# nano_bt_usb.net
KiCad netlist of a schematic drawn in EAGLE
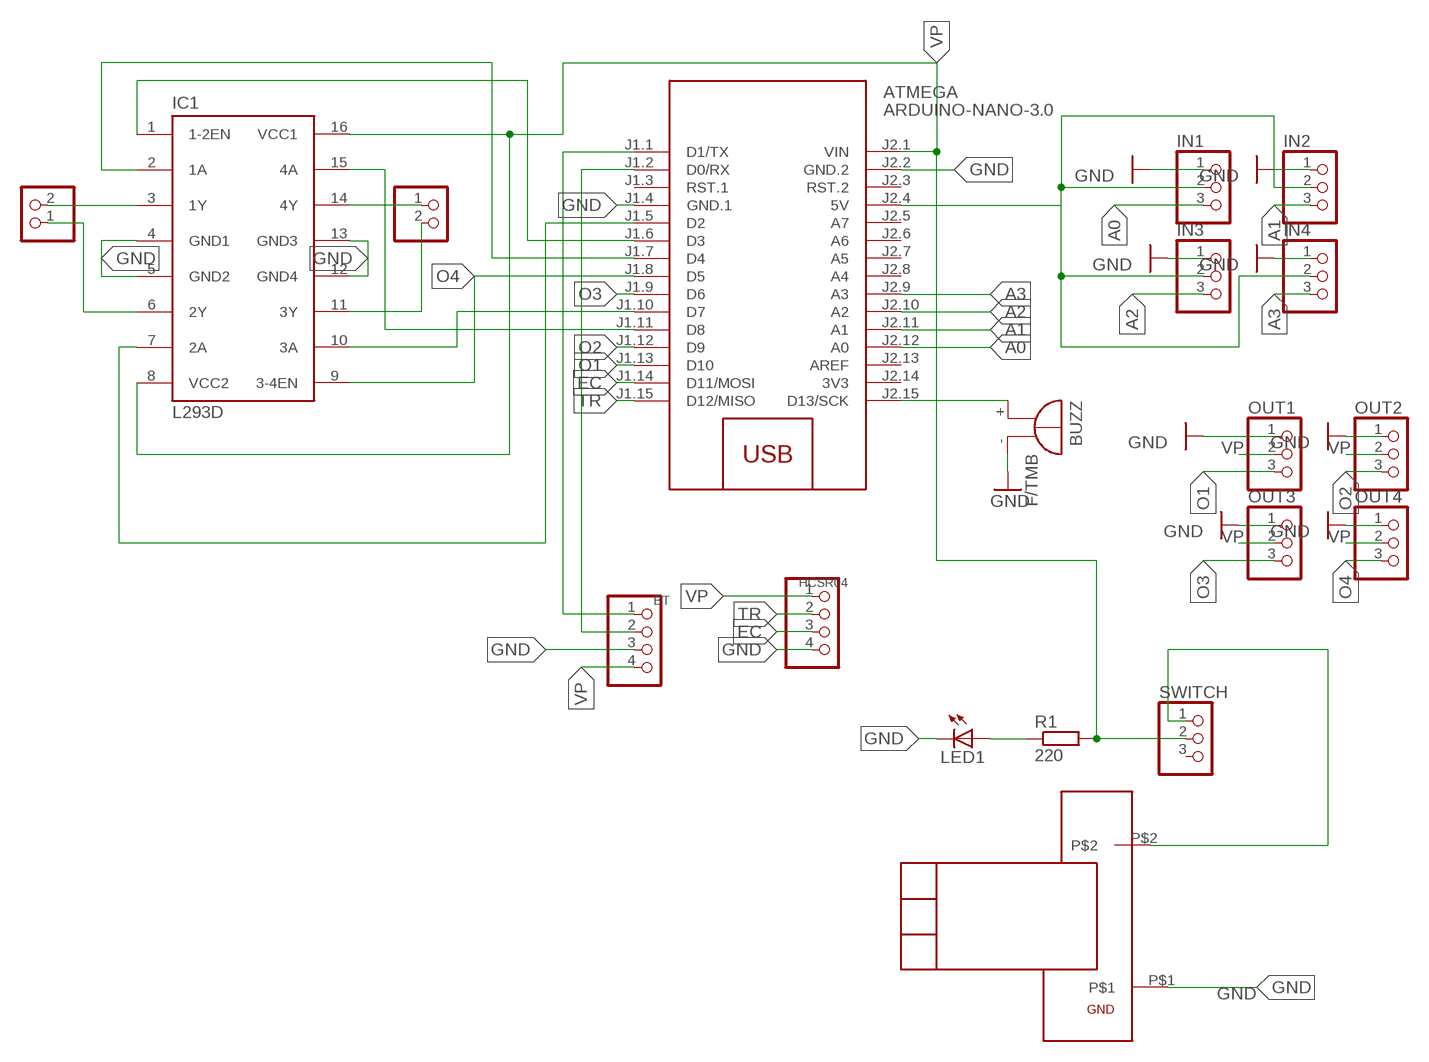
[diagram p0: schematic, sheet 1]

(export (version "E")
  (design (tool "Eeschema 10.0.6"))
  (components
    (comp (ref "ATMEGA")
      (value "ARDUINO-NANO-3.0")
      (footprint "eagle-import:ARDUINO-NANO-3.0")
      (libsource (lib "eagle-import") (part "ARDUINO-NANO-3.0"))
    )
    (comp (ref "BT")
      (value "PINHD-1X4")
      (footprint "eagle-import:1X04")
      (libsource (lib "eagle-import") (part "PINHD-1X4"))
    )
    (comp (ref "BUZZ")
      (value "F/TMB")
      (footprint "eagle-import:F_TMB")
      (libsource (lib "eagle-import") (part "F/TMB"))
    )
    (comp (ref "HCSR04")
      (value "PINHD-1X4")
      (footprint "eagle-import:1X04")
      (libsource (lib "eagle-import") (part "PINHD-1X4"))
    )
    (comp (ref "IC1")
      (value "L293D")
      (footprint "eagle-import:DIL16")
      (libsource (lib "eagle-import") (part "L293D"))
    )
    (comp (ref "IN1")
      (value "PINHD-1X3")
      (footprint "eagle-import:1X03")
      (libsource (lib "eagle-import") (part "PINHD-1X3"))
    )
    (comp (ref "IN2")
      (value "PINHD-1X3")
      (footprint "eagle-import:1X03")
      (libsource (lib "eagle-import") (part "PINHD-1X3"))
    )
    (comp (ref "IN3")
      (value "PINHD-1X3")
      (footprint "eagle-import:1X03")
      (libsource (lib "eagle-import") (part "PINHD-1X3"))
    )
    (comp (ref "IN4")
      (value "PINHD-1X3")
      (footprint "eagle-import:1X03")
      (libsource (lib "eagle-import") (part "PINHD-1X3"))
    )
    (comp (ref "LED1")
      (value "LED3MM")
      (footprint "eagle-import:LED3MM")
      (libsource (lib "eagle-import") (part "LED3MM"))
    )
    (comp (ref "MT1")
      (value "PINHD-1X2")
      (footprint "eagle-import:1X02")
      (libsource (lib "eagle-import") (part "PINHD-1X2"))
    )
    (comp (ref "MT2")
      (value "PINHD-1X2")
      (footprint "eagle-import:1X02")
      (libsource (lib "eagle-import") (part "PINHD-1X2"))
    )
    (comp (ref "OUT1")
      (value "PINHD-1X3")
      (footprint "eagle-import:1X03")
      (libsource (lib "eagle-import") (part "PINHD-1X3"))
    )
    (comp (ref "OUT2")
      (value "PINHD-1X3")
      (footprint "eagle-import:1X03")
      (libsource (lib "eagle-import") (part "PINHD-1X3"))
    )
    (comp (ref "OUT3")
      (value "PINHD-1X3")
      (footprint "eagle-import:1X03")
      (libsource (lib "eagle-import") (part "PINHD-1X3"))
    )
    (comp (ref "OUT4")
      (value "PINHD-1X3")
      (footprint "eagle-import:1X03")
      (libsource (lib "eagle-import") (part "PINHD-1X3"))
    )
    (comp (ref "R1")
      (value "220")
      (footprint "eagle-import:0204_7")
      (libsource (lib "eagle-import") (part "R-EU_0204/7"))
    )
    (comp (ref "SWITCH")
      (value "PINHD-1X3")
      (footprint "eagle-import:1X03")
      (libsource (lib "eagle-import") (part "adafruit_arduino_PINHD-1X3"))
    )
    (comp (ref "U$1")
      (value "MICROUSBMODUL")
      (footprint "eagle-import:MICROUSB")
      (libsource (lib "eagle-import") (part "MICROUSBMODUL"))
    )
  )
  (nets
    (net (code "1") (name "/3V3") (class "Default")
      (node (ref "ATMEGA") (pin "J2.14") (pinfunction "3V3_J2.14") (pintype "power_in"))
    )
    (net (code "2") (name "A0") (class "Default")
      (node (ref "ATMEGA") (pin "J2.12") (pinfunction "A0_J2.12") (pintype "bidirectional"))
      (node (ref "IN1") (pin "3") (pinfunction "3_3") (pintype "passive"))
    )
    (net (code "3") (name "A1") (class "Default")
      (node (ref "ATMEGA") (pin "J2.11") (pinfunction "A1_J2.11") (pintype "bidirectional"))
      (node (ref "IN2") (pin "3") (pinfunction "3_3") (pintype "passive"))
    )
    (net (code "4") (name "A2") (class "Default")
      (node (ref "ATMEGA") (pin "J2.10") (pinfunction "A2_J2.10") (pintype "bidirectional"))
      (node (ref "IN3") (pin "3") (pinfunction "3_3") (pintype "passive"))
    )
    (net (code "5") (name "A3") (class "Default")
      (node (ref "ATMEGA") (pin "J2.9") (pinfunction "A3_J2.9") (pintype "bidirectional"))
      (node (ref "IN4") (pin "3") (pinfunction "3_3") (pintype "passive"))
    )
    (net (code "6") (name "EC") (class "Default")
      (node (ref "ATMEGA") (pin "J1.14") (pinfunction "D11/MOSI_J1.14") (pintype "bidirectional"))
      (node (ref "HCSR04") (pin "3") (pinfunction "3_3") (pintype "passive"))
    )
    (net (code "7") (name "GND") (class "Default")
      (node (ref "ATMEGA") (pin "J1.4") (pinfunction "GND.1_J1.4") (pintype "power_in"))
      (node (ref "ATMEGA") (pin "J2.2") (pinfunction "GND.2_J2.2") (pintype "power_in"))
      (node (ref "BT") (pin "3") (pinfunction "3_3") (pintype "passive"))
      (node (ref "BUZZ") (pin "-") (pinfunction "-_-") (pintype "passive"))
      (node (ref "HCSR04") (pin "4") (pinfunction "4_4") (pintype "passive"))
      (node (ref "IC1") (pin "12") (pinfunction "GND4_12") (pintype "power_in"))
      (node (ref "IC1") (pin "13") (pinfunction "GND3_13") (pintype "power_in"))
      (node (ref "IC1") (pin "4") (pinfunction "GND1_4") (pintype "power_in"))
      (node (ref "IC1") (pin "5") (pinfunction "GND2_5") (pintype "power_in"))
      (node (ref "IN1") (pin "1") (pinfunction "1_1") (pintype "passive"))
      (node (ref "IN2") (pin "1") (pinfunction "1_1") (pintype "passive"))
      (node (ref "IN3") (pin "1") (pinfunction "1_1") (pintype "passive"))
      (node (ref "IN4") (pin "1") (pinfunction "1_1") (pintype "passive"))
      (node (ref "LED1") (pin "K") (pinfunction "C_K") (pintype "passive"))
      (node (ref "OUT1") (pin "1") (pinfunction "1_1") (pintype "passive"))
      (node (ref "OUT2") (pin "1") (pinfunction "1_1") (pintype "passive"))
      (node (ref "OUT3") (pin "1") (pinfunction "1_1") (pintype "passive"))
      (node (ref "OUT4") (pin "1") (pinfunction "1_1") (pintype "passive"))
      (node (ref "U$1") (pin "P$1") (pinfunction "P$1_P$1") (pintype "bidirectional"))
    )
    (net (code "8") (name "Net-(ATMEGA-5V)") (class "Default")
      (node (ref "ATMEGA") (pin "J2.4") (pinfunction "5V_J2.4") (pintype "power_in"))
      (node (ref "IN1") (pin "2") (pinfunction "2_2") (pintype "passive"))
      (node (ref "IN2") (pin "2") (pinfunction "2_2") (pintype "passive"))
      (node (ref "IN3") (pin "2") (pinfunction "2_2") (pintype "passive"))
      (node (ref "IN4") (pin "2") (pinfunction "2_2") (pintype "passive"))
    )
    (net (code "9") (name "Net-(ATMEGA-D0{slash}RX)") (class "Default")
      (node (ref "ATMEGA") (pin "J1.2") (pinfunction "D0/RX_J1.2") (pintype "bidirectional"))
      (node (ref "BT") (pin "2") (pinfunction "2_2") (pintype "passive"))
    )
    (net (code "10") (name "Net-(ATMEGA-D1{slash}TX)") (class "Default")
      (node (ref "ATMEGA") (pin "J1.1") (pinfunction "D1/TX_J1.1") (pintype "bidirectional"))
      (node (ref "BT") (pin "1") (pinfunction "1_1") (pintype "passive"))
    )
    (net (code "11") (name "Net-(ATMEGA-D2)") (class "Default")
      (node (ref "ATMEGA") (pin "J1.5") (pinfunction "D2_J1.5") (pintype "bidirectional"))
      (node (ref "IC1") (pin "7") (pinfunction "2A_7") (pintype "input"))
    )
    (net (code "12") (name "Net-(ATMEGA-D3)") (class "Default")
      (node (ref "ATMEGA") (pin "J1.6") (pinfunction "D3_J1.6") (pintype "bidirectional"))
      (node (ref "IC1") (pin "1") (pinfunction "1-2EN_1") (pintype "input"))
    )
    (net (code "13") (name "Net-(ATMEGA-D4)") (class "Default")
      (node (ref "ATMEGA") (pin "J1.7") (pinfunction "D4_J1.7") (pintype "bidirectional"))
      (node (ref "IC1") (pin "2") (pinfunction "1A_2") (pintype "input"))
    )
    (net (code "14") (name "Net-(ATMEGA-D7)") (class "Default")
      (node (ref "ATMEGA") (pin "J1.10") (pinfunction "D7_J1.10") (pintype "bidirectional"))
      (node (ref "IC1") (pin "10") (pinfunction "3A_10") (pintype "input"))
    )
    (net (code "15") (name "Net-(ATMEGA-D8)") (class "Default")
      (node (ref "ATMEGA") (pin "J1.11") (pinfunction "D8_J1.11") (pintype "bidirectional"))
      (node (ref "IC1") (pin "15") (pinfunction "4A_15") (pintype "input"))
    )
    (net (code "16") (name "Net-(ATMEGA-D13{slash}SCK)") (class "Default")
      (node (ref "ATMEGA") (pin "J2.15") (pinfunction "D13/SCK_J2.15") (pintype "bidirectional"))
      (node (ref "BUZZ") (pin "+") (pinfunction "+_+") (pintype "passive"))
    )
    (net (code "17") (name "Net-(IC1-1Y)") (class "Default")
      (node (ref "IC1") (pin "3") (pinfunction "1Y_3") (pintype "output"))
      (node (ref "MT1") (pin "2") (pinfunction "2_2") (pintype "passive"))
    )
    (net (code "18") (name "Net-(IC1-2Y)") (class "Default")
      (node (ref "IC1") (pin "6") (pinfunction "2Y_6") (pintype "output"))
      (node (ref "MT1") (pin "1") (pinfunction "1_1") (pintype "passive"))
    )
    (net (code "19") (name "Net-(IC1-3Y)") (class "Default")
      (node (ref "IC1") (pin "11") (pinfunction "3Y_11") (pintype "output"))
      (node (ref "MT2") (pin "2") (pinfunction "2_2") (pintype "passive"))
    )
    (net (code "20") (name "Net-(IC1-4Y)") (class "Default")
      (node (ref "IC1") (pin "14") (pinfunction "4Y_14") (pintype "output"))
      (node (ref "MT2") (pin "1") (pinfunction "1_1") (pintype "passive"))
    )
    (net (code "21") (name "Net-(LED1-PadA)") (class "Default")
      (node (ref "LED1") (pin "A") (pinfunction "A_A") (pintype "passive"))
      (node (ref "R1") (pin "1") (pinfunction "1_1") (pintype "passive"))
    )
    (net (code "22") (name "Net-(SWITCH-Pad1)") (class "Default")
      (node (ref "SWITCH") (pin "1") (pinfunction "1_1") (pintype "passive"))
      (node (ref "U$1") (pin "P$2") (pinfunction "P$2_P$2") (pintype "bidirectional"))
    )
    (net (code "23") (name "O1") (class "Default")
      (node (ref "ATMEGA") (pin "J1.13") (pinfunction "D10_J1.13") (pintype "bidirectional"))
      (node (ref "OUT1") (pin "3") (pinfunction "3_3") (pintype "passive"))
    )
    (net (code "24") (name "O2") (class "Default")
      (node (ref "ATMEGA") (pin "J1.12") (pinfunction "D9_J1.12") (pintype "bidirectional"))
      (node (ref "OUT2") (pin "3") (pinfunction "3_3") (pintype "passive"))
    )
    (net (code "25") (name "O3") (class "Default")
      (node (ref "ATMEGA") (pin "J1.9") (pinfunction "D6_J1.9") (pintype "bidirectional"))
      (node (ref "OUT3") (pin "3") (pinfunction "3_3") (pintype "passive"))
    )
    (net (code "26") (name "O4") (class "Default")
      (node (ref "ATMEGA") (pin "J1.8") (pinfunction "D5_J1.8") (pintype "bidirectional"))
      (node (ref "IC1") (pin "9") (pinfunction "3-4EN_9") (pintype "input"))
      (node (ref "OUT4") (pin "3") (pinfunction "3_3") (pintype "passive"))
    )
    (net (code "27") (name "TR") (class "Default")
      (node (ref "ATMEGA") (pin "J1.15") (pinfunction "D12/MISO_J1.15") (pintype "bidirectional"))
      (node (ref "HCSR04") (pin "2") (pinfunction "2_2") (pintype "passive"))
    )
    (net (code "28") (name "VP") (class "Default")
      (node (ref "ATMEGA") (pin "J2.1") (pinfunction "VIN_J2.1") (pintype "power_in"))
      (node (ref "BT") (pin "4") (pinfunction "4_4") (pintype "passive"))
      (node (ref "HCSR04") (pin "1") (pinfunction "1_1") (pintype "passive"))
      (node (ref "IC1") (pin "16") (pinfunction "VCC1_16") (pintype "power_in"))
      (node (ref "IC1") (pin "8") (pinfunction "VCC2_8") (pintype "power_in"))
      (node (ref "OUT1") (pin "2") (pinfunction "2_2") (pintype "passive"))
      (node (ref "OUT2") (pin "2") (pinfunction "2_2") (pintype "passive"))
      (node (ref "OUT3") (pin "2") (pinfunction "2_2") (pintype "passive"))
      (node (ref "OUT4") (pin "2") (pinfunction "2_2") (pintype "passive"))
      (node (ref "R1") (pin "2") (pinfunction "2_2") (pintype "passive"))
      (node (ref "SWITCH") (pin "2") (pinfunction "2_2") (pintype "passive"))
    )
    (net (code "29") (name "unconnected-(ATMEGA-A4-PadJ2.8)") (class "Default")
      (node (ref "ATMEGA") (pin "J2.8") (pinfunction "A4_J2.8") (pintype "bidirectional"))
    )
    (net (code "30") (name "unconnected-(ATMEGA-A5-PadJ2.7)") (class "Default")
      (node (ref "ATMEGA") (pin "J2.7") (pinfunction "A5_J2.7") (pintype "bidirectional"))
    )
    (net (code "31") (name "unconnected-(ATMEGA-A6-PadJ2.6)") (class "Default")
      (node (ref "ATMEGA") (pin "J2.6") (pinfunction "A6_J2.6") (pintype "bidirectional"))
    )
    (net (code "32") (name "unconnected-(ATMEGA-A7-PadJ2.5)") (class "Default")
      (node (ref "ATMEGA") (pin "J2.5") (pinfunction "A7_J2.5") (pintype "bidirectional"))
    )
    (net (code "33") (name "unconnected-(ATMEGA-AREF-PadJ2.13)") (class "Default")
      (node (ref "ATMEGA") (pin "J2.13") (pinfunction "AREF_J2.13") (pintype "bidirectional"))
    )
    (net (code "34") (name "unconnected-(ATMEGA-RST.1-PadJ1.3)") (class "Default")
      (node (ref "ATMEGA") (pin "J1.3") (pinfunction "RST.1_J1.3") (pintype "bidirectional"))
    )
    (net (code "35") (name "unconnected-(ATMEGA-RST.2-PadJ2.3)") (class "Default")
      (node (ref "ATMEGA") (pin "J2.3") (pinfunction "RST.2_J2.3") (pintype "bidirectional"))
    )
    (net (code "36") (name "unconnected-(SWITCH-Pad3)") (class "Default")
      (node (ref "SWITCH") (pin "3") (pinfunction "3_3") (pintype "passive"))
    )
  )
)
